# Schematics.net
KiCad netlist of a schematic drawn in Altium Designer
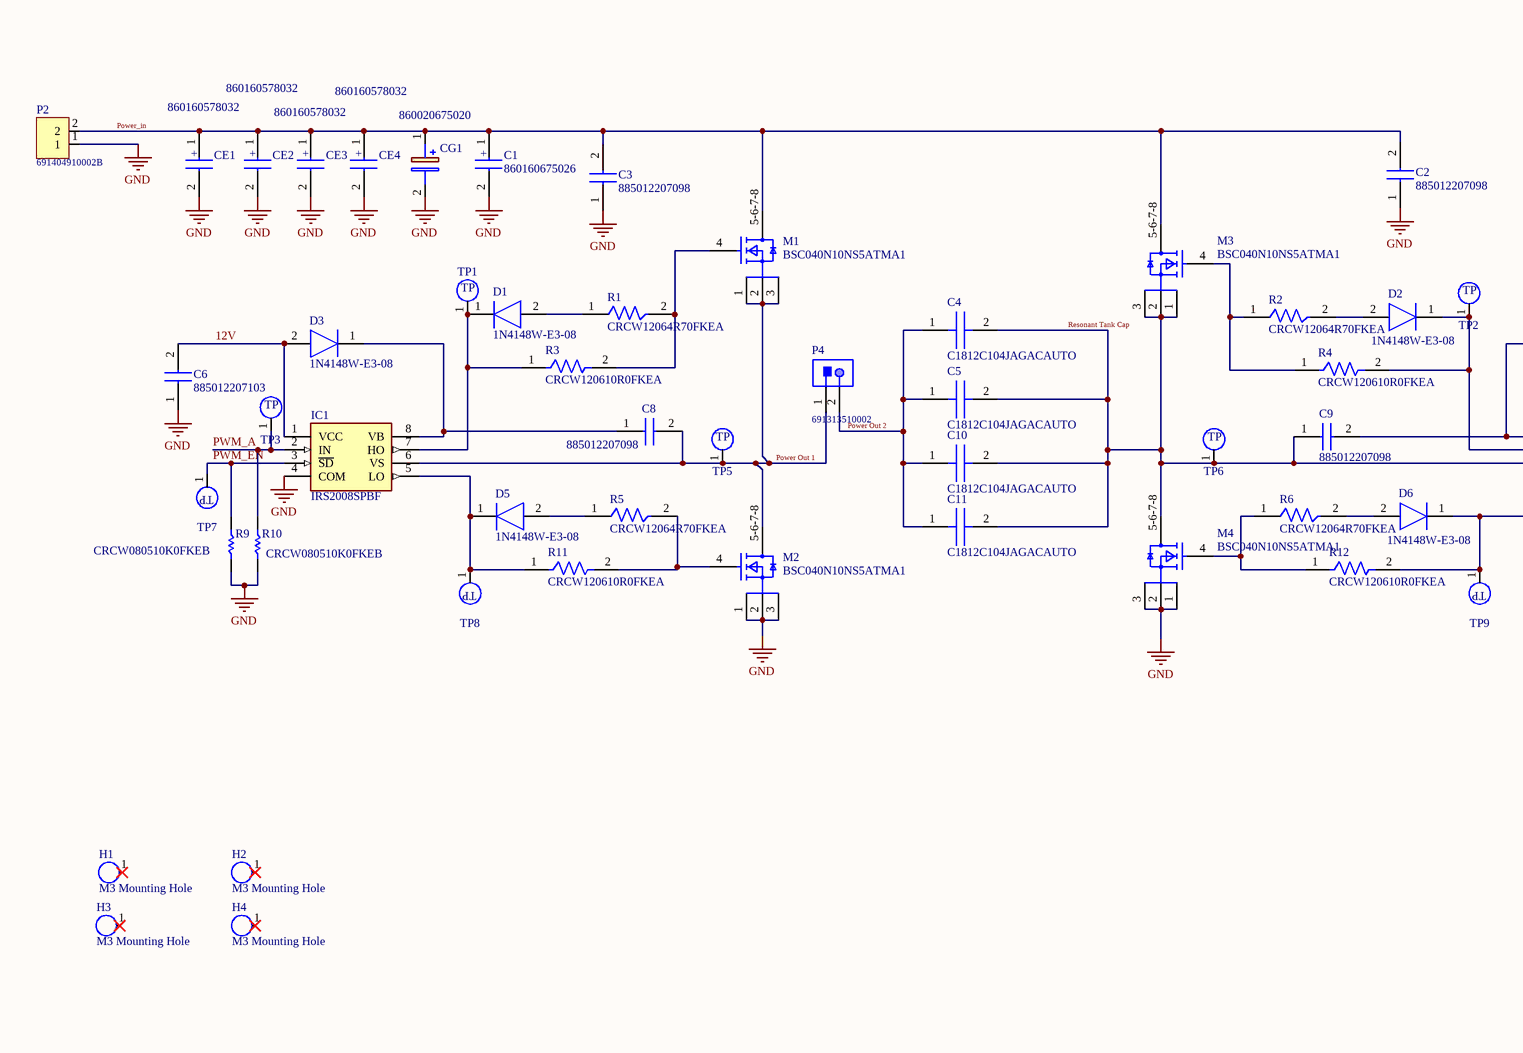
[diagram p0: Schematics.SchDoc, left]
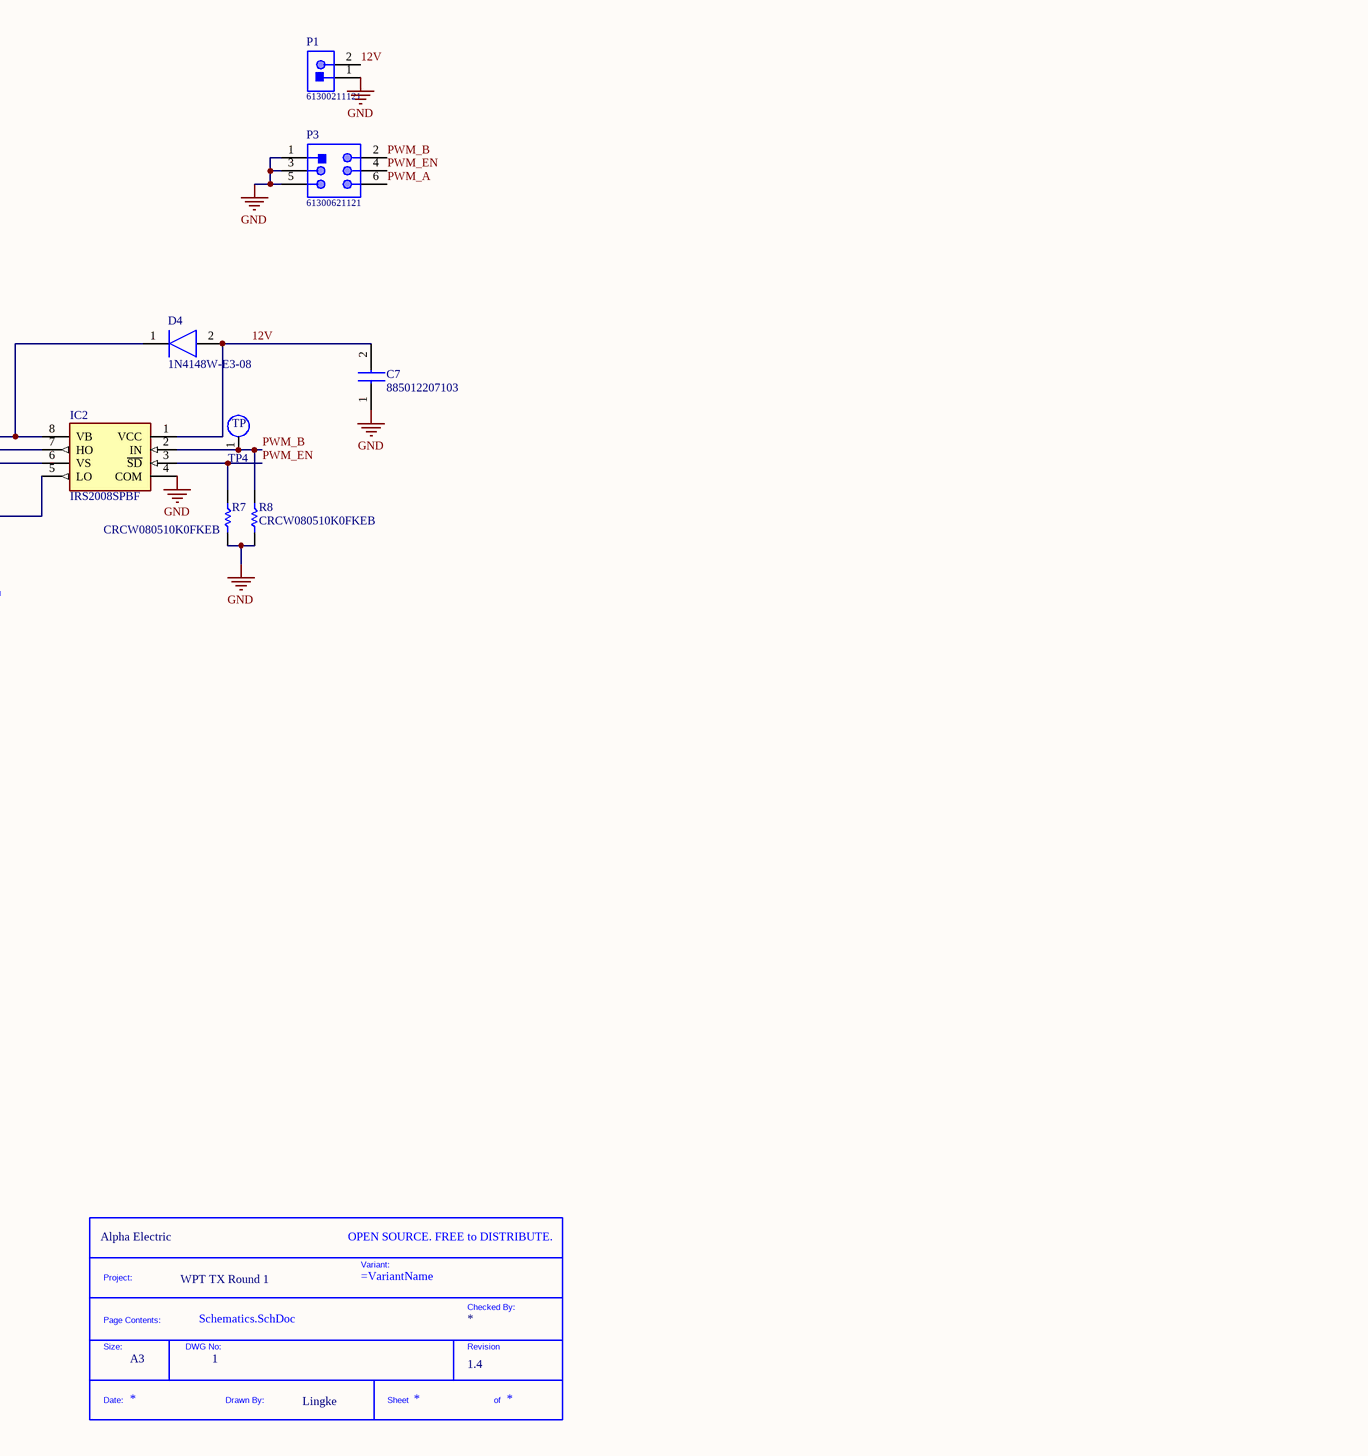
[diagram p1: Schematics.SchDoc, middle]
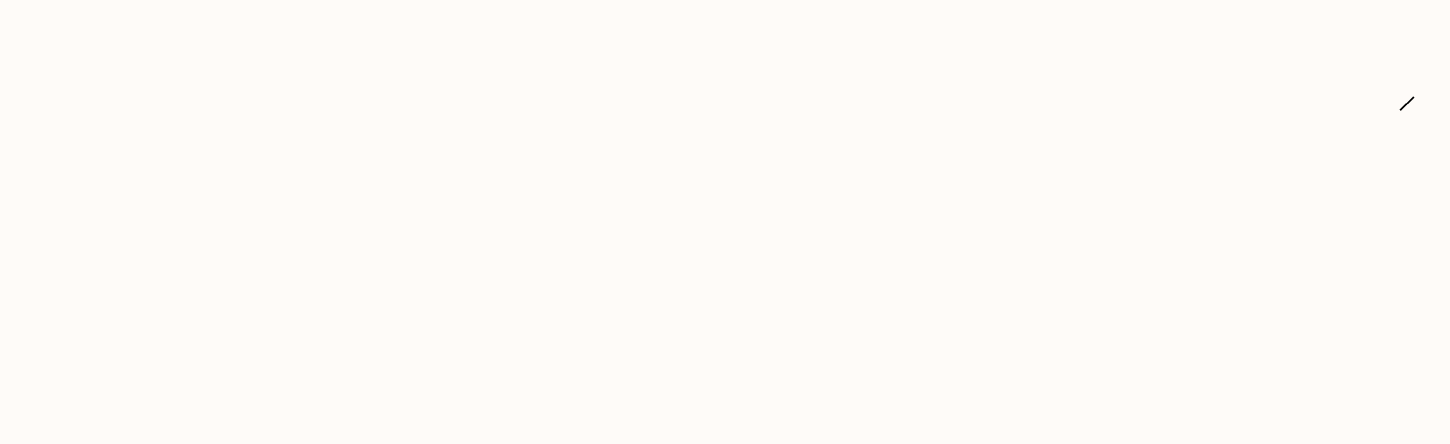
[diagram p2: Schematics.SchDoc, right]

(export (version "E")
  (design (tool "Eeschema 10.0.6"))
  (components
    (comp (ref "*")
      (value "Title_Block")
      (description "Standard Title Block.")
      (fields
        (field (name "PROJECT NAME") "WPT TX Round 1")
        (field (name "COMPANY") "Alpha Electric")
        (field (name "DRAWN BY") "Lingke")
        (field (name "REVISION") "1.4")
        (field (name "DWG NO") "1")
        (field (name "SIZE") "A3")
        (field (name "CHECKED BY") "*")
      )
      (libsource (lib "Symbol Library") (part "Title_Block"))
    )
    (comp (ref "C1")
      (value "860160675026")
      (footprint "SamacSys:CAPPRD500W62D1000H1750")
      (description "Capacitor 220uF/50V")
      (libsource (lib "Symbol Library") (part "Input Cap 220uF"))
    )
    (comp (ref "C2")
      (value "885012207098")
      (footprint "SamacSys:CAPC2012X90N")
      (description "Capacitor 0.1uF/50V X7R")
      (fields (field (name "MOUSER2 PART NUMBER") "710-885012207098"))
      (libsource (lib "Symbol Library") (part "Input Cap 100nF"))
    )
    (comp (ref "C3")
      (value "885012207098")
      (footprint "SamacSys:CAPC2012X90N")
      (description "Capacitor 0.1uF/50V X7R")
      (fields (field (name "MOUSER2 PART NUMBER") "710-885012207098"))
      (libsource (lib "Symbol Library") (part "Input Cap 100nF"))
    )
    (comp (ref "C4")
      (value "C1812C104JAGACAUTO")
      (footprint "SamacSys:CAPC4532X220N")
      (description "Resistor")
      (libsource (lib "Symbol Library") (part "Resonant Tank Cap"))
    )
    (comp (ref "C5")
      (value "C1812C104JAGACAUTO")
      (footprint "SamacSys:CAPC4532X220N")
      (description "Resistor")
      (libsource (lib "Symbol Library") (part "Resonant Tank Cap"))
    )
    (comp (ref "C6")
      (value "885012207103")
      (footprint "SamacSys:CAPC2012X135N")
      (description "Capacitor")
      (libsource (lib "Symbol Library") (part "12V Fiter Cap"))
    )
    (comp (ref "C7")
      (value "885012207103")
      (footprint "SamacSys:CAPC2012X135N")
      (description "Capacitor")
      (libsource (lib "Symbol Library") (part "12V Fiter Cap"))
    )
    (comp (ref "C8")
      (value "885012207098")
      (footprint "SamacSys:CAPC2012X90N")
      (description "Capacitor 0.1uF/50V X7R")
      (fields (field (name "MOUSER2 PART NUMBER") "710-885012207098"))
      (libsource (lib "Symbol Library") (part "Input Cap 100nF"))
    )
    (comp (ref "C9")
      (value "885012207098")
      (footprint "SamacSys:CAPC2012X90N")
      (description "Capacitor 0.1uF/50V X7R")
      (fields (field (name "MOUSER2 PART NUMBER") "710-885012207098"))
      (libsource (lib "") (part "Input Cap 100nF_1"))
    )
    (comp (ref "C10")
      (value "C1812C104JAGACAUTO")
      (footprint "SamacSys:CAPC4532X220N")
      (description "Resistor")
      (libsource (lib "Symbol Library") (part "Resonant Tank Cap"))
    )
    (comp (ref "C11")
      (value "C1812C104JAGACAUTO")
      (footprint "SamacSys:CAPC4532X220N")
      (description "Resistor")
      (libsource (lib "Symbol Library") (part "Resonant Tank Cap"))
    )
    (comp (ref "CE1")
      (value "860160578032")
      (footprint "SamacSys:CAPPRD500W62D1300H2650")
      (description "Capacitor 1000uF Input Filtering")
      (libsource (lib "Symbol Library") (part "1000uF Input Cap"))
    )
    (comp (ref "CE2")
      (value "860160578032")
      (footprint "SamacSys:CAPPRD500W62D1300H2650")
      (description "Capacitor 1000uF Input Filtering")
      (libsource (lib "Symbol Library") (part "1000uF Input Cap"))
    )
    (comp (ref "CE3")
      (value "860160578032")
      (footprint "SamacSys:CAPPRD500W62D1300H2650")
      (description "Capacitor 1000uF Input Filtering")
      (libsource (lib "Symbol Library") (part "1000uF Input Cap"))
    )
    (comp (ref "CE4")
      (value "860160578032")
      (footprint "SamacSys:CAPPRD500W62D1300H2650")
      (description "Capacitor 1000uF Input Filtering")
      (libsource (lib "Symbol Library") (part "1000uF Input Cap"))
    )
    (comp (ref "CG1")
      (value "860020675020")
      (footprint "SamacSys:CAPPRD500W62D1000H1400")
      (description "Capacitor Polarised")
      (libsource (lib "Symbol Library") (part "Ground Splitting Cap"))
    )
    (comp (ref "D1")
      (value "1N4148W-E3-08")
      (footprint "SamacSys:SOD3716X135N")
      (description "Diode")
      (fields (field (name "MOUSER2 PART NUMBER") "78-1N4148W-E3-08"))
      (libsource (lib "Symbol Library") (part "BootStrap Diode"))
    )
    (comp (ref "D2")
      (value "1N4148W-E3-08")
      (footprint "SamacSys:SOD3716X135N")
      (description "Diode")
      (fields (field (name "MOUSER2 PART NUMBER") "78-1N4148W-E3-08"))
      (libsource (lib "Symbol Library") (part "BootStrap Diode"))
    )
    (comp (ref "D3")
      (value "1N4148W-E3-08")
      (footprint "SamacSys:SOD3716X135N")
      (description "Diode")
      (fields (field (name "MOUSER2 PART NUMBER") "78-1N4148W-E3-08"))
      (libsource (lib "Symbol Library") (part "BootStrap Diode"))
    )
    (comp (ref "D4")
      (value "1N4148W-E3-08")
      (footprint "SamacSys:SOD3716X135N")
      (description "Diode")
      (fields (field (name "MOUSER2 PART NUMBER") "78-1N4148W-E3-08"))
      (libsource (lib "Symbol Library") (part "BootStrap Diode"))
    )
    (comp (ref "D5")
      (value "1N4148W-E3-08")
      (footprint "SamacSys:SOD3716X135N")
      (description "Diode")
      (fields (field (name "MOUSER2 PART NUMBER") "78-1N4148W-E3-08"))
      (libsource (lib "Symbol Library") (part "BootStrap Diode"))
    )
    (comp (ref "D6")
      (value "1N4148W-E3-08")
      (footprint "SamacSys:SOD3716X135N")
      (description "Diode")
      (fields (field (name "MOUSER2 PART NUMBER") "78-1N4148W-E3-08"))
      (libsource (lib "Symbol Library") (part "BootStrap Diode"))
    )
    (comp (ref "H1")
      (value "M3 Mounting Hole")
      (footprint "M3 Hole")
      (libsource (lib "Symbol Library") (part "M3_Mounting_hole"))
    )
    (comp (ref "H2")
      (value "M3 Mounting Hole")
      (footprint "M3 Hole")
      (libsource (lib "Symbol Library") (part "M3_Mounting_hole"))
    )
    (comp (ref "H3")
      (value "M3 Mounting Hole")
      (footprint "M3 Hole")
      (libsource (lib "Symbol Library") (part "M3_Mounting_hole"))
    )
    (comp (ref "H4")
      (value "M3 Mounting Hole")
      (footprint "M3 Hole")
      (libsource (lib "Symbol Library") (part "M3_Mounting_hole"))
    )
    (comp (ref "IC1")
      (value "IRS2008SPBF")
      (footprint "SamacSys:SOIC127P600X175-8N")
      (description "Integrated Circuit")
      (libsource (lib "") (part "Gate Driver IC_1"))
    )
    (comp (ref "IC2")
      (value "IRS2008SPBF")
      (footprint "SamacSys:SOIC127P600X175-8N")
      (description "Integrated Circuit")
      (libsource (lib "Symbol Library") (part "Gate Driver IC"))
    )
    (comp (ref "M1")
      (value "BSC040N10NS5ATMA1")
      (footprint "FP-PG-TDSON-8-MFG")
      (description "MOSFET N-CH 100V 100A 8TDSON")
      (fields
        (field (name "MANUFACTURER") "Infineon")
        (field (name "OCTOPART") "https://octopart.com/bsc040n10ns5atma1-infineon-52825711")
      )
      (libsource (lib "Symbol Library") (part "Mosfet Switcher"))
    )
    (comp (ref "M2")
      (value "BSC040N10NS5ATMA1")
      (footprint "FP-PG-TDSON-8-MFG")
      (description "MOSFET N-CH 100V 100A 8TDSON")
      (fields
        (field (name "MANUFACTURER") "Infineon")
        (field (name "OCTOPART") "https://octopart.com/bsc040n10ns5atma1-infineon-52825711")
      )
      (libsource (lib "Symbol Library") (part "Mosfet Switcher"))
    )
    (comp (ref "M3")
      (value "BSC040N10NS5ATMA1")
      (footprint "FP-PG-TDSON-8-MFG")
      (description "MOSFET N-CH 100V 100A 8TDSON")
      (fields
        (field (name "MANUFACTURER") "Infineon")
        (field (name "OCTOPART") "https://octopart.com/bsc040n10ns5atma1-infineon-52825711")
      )
      (libsource (lib "Symbol Library") (part "Mosfet Switcher"))
    )
    (comp (ref "M4")
      (value "BSC040N10NS5ATMA1")
      (footprint "FP-PG-TDSON-8-MFG")
      (description "MOSFET N-CH 100V 100A 8TDSON")
      (fields
        (field (name "MANUFACTURER") "Infineon")
        (field (name "OCTOPART") "https://octopart.com/bsc040n10ns5atma1-infineon-52825711")
      )
      (libsource (lib "Symbol Library") (part "Mosfet Switcher"))
    )
    (comp (ref "P1")
      (value "61300211121")
      (footprint "61300211121")
      (description "THT Vertical Pin Header WR-PHD, Pitch 2.54 mm, Single Row, 2 pins")
      (fields (field (name "MANUFACTURER") "Wurth Elektronik") (field (name "PUBLISHER") "WurthElektronik"))
      (libsource (lib "Symbol Library") (part "12V Input"))
    )
    (comp (ref "P2")
      (value "691404910002B")
      (footprint "691404910002B")
      (description "Serie 4049 B - 7.50mm Screwless Clamp Power Connector WR-TBL, 2 pin")
      (fields (field (name "MANUFACTURER") "Wurth Elektronik") (field (name "PUBLISHER") "WurthElektronik"))
      (libsource (lib "Symbol Library") (part "Power Input"))
    )
    (comp (ref "P3")
      (value "61300621121")
      (footprint "61300621121")
      (description "THT Vertical Pin Header WR-PHD, Pitch 2.54 mm, Dual Row, 6 pins")
      (fields (field (name "MANUFACTURER") "Wurth Elektronik") (field (name "PUBLISHER") "WurthElektronik"))
      (libsource (lib "Symbol Library") (part "PWM Input Dual Pin"))
    )
    (comp (ref "P4")
      (value "691313510002")
      (footprint "691313510002")
      (description "Serie 313 - 5.08mm Close Horizontal PCB Header WR-TBL, 2 pin")
      (fields (field (name "MANUFACTURER") "Wurth Elektronik") (field (name "PUBLISHER") "WurthElektronik"))
      (libsource (lib "Symbol Library") (part "Power Output"))
    )
    (comp (ref "R1")
      (value "CRCW12064R70FKEA")
      (footprint "FP-CRCW1206-e3-IPC_A")
      (description "RES Thick Film, 4.7Ω, 1%, 0.25W, 100ppm/°C, 1206")
      (fields (field (name "TOLERANCE") "1%"))
      (libsource (lib "") (part "MOSFET Gate Fast-off Resistor 4.7Ohm_1"))
    )
    (comp (ref "R2")
      (value "CRCW12064R70FKEA")
      (footprint "FP-CRCW1206-e3-IPC_A")
      (description "RES Thick Film, 4.7Ω, 1%, 0.25W, 100ppm/°C, 1206")
      (fields (field (name "TOLERANCE") "1%"))
      (libsource (lib "Symbol Library") (part "MOSFET Gate Fast-off Resistor 4.7Ohm"))
    )
    (comp (ref "R3")
      (value "CRCW120610R0FKEA")
      (footprint "FP-CRCW1206-e3-IPC_A")
      (description "RES Thick Film, 10Ω, 1%, 0.25W, 100ppm/°C, 1206")
      (fields (field (name "TOLERANCE") "1%"))
      (libsource (lib "Symbol Library") (part "MOSFET Gate Resistor 10Ohm"))
    )
    (comp (ref "R4")
      (value "CRCW120610R0FKEA")
      (footprint "FP-CRCW1206-e3-IPC_A")
      (description "RES Thick Film, 10Ω, 1%, 0.25W, 100ppm/°C, 1206")
      (fields (field (name "TOLERANCE") "1%"))
      (libsource (lib "") (part "MOSFET Gate Resistor 10Ohm_1"))
    )
    (comp (ref "R5")
      (value "CRCW12064R70FKEA")
      (footprint "FP-CRCW1206-e3-IPC_A")
      (description "RES Thick Film, 4.7Ω, 1%, 0.25W, 100ppm/°C, 1206")
      (fields (field (name "TOLERANCE") "1%"))
      (libsource (lib "") (part "MOSFET Gate Fast-off Resistor 4.7Ohm_1"))
    )
    (comp (ref "R6")
      (value "CRCW12064R70FKEA")
      (footprint "FP-CRCW1206-e3-IPC_A")
      (description "RES Thick Film, 4.7Ω, 1%, 0.25W, 100ppm/°C, 1206")
      (fields (field (name "TOLERANCE") "1%"))
      (libsource (lib "Symbol Library") (part "MOSFET Gate Fast-off Resistor 4.7Ohm"))
    )
    (comp (ref "R7")
      (value "CRCW080510K0FKEB")
      (footprint "RESC2013X50X30ML20T20")
      (fields (field (name "MANUFACTURER") "Vishay Dale"))
      (libsource (lib "Symbol Library") (part "PWM Pull Down Resistor"))
    )
    (comp (ref "R8")
      (value "CRCW080510K0FKEB")
      (footprint "RESC2013X50X30ML20T20")
      (fields (field (name "MANUFACTURER") "Vishay Dale"))
      (libsource (lib "Symbol Library") (part "PWM Pull Down Resistor"))
    )
    (comp (ref "R9")
      (value "CRCW080510K0FKEB")
      (footprint "RESC2013X50X30ML20T20")
      (fields (field (name "MANUFACTURER") "Vishay Dale"))
      (libsource (lib "Symbol Library") (part "PWM Pull Down Resistor"))
    )
    (comp (ref "R10")
      (value "CRCW080510K0FKEB")
      (footprint "RESC2013X50X30ML20T20")
      (fields (field (name "MANUFACTURER") "Vishay Dale"))
      (libsource (lib "Symbol Library") (part "PWM Pull Down Resistor"))
    )
    (comp (ref "R11")
      (value "CRCW120610R0FKEA")
      (footprint "FP-CRCW1206-e3-IPC_A")
      (description "RES Thick Film, 10Ω, 1%, 0.25W, 100ppm/°C, 1206")
      (fields (field (name "TOLERANCE") "1%"))
      (libsource (lib "Symbol Library") (part "MOSFET Gate Resistor 10Ohm"))
    )
    (comp (ref "R12")
      (value "CRCW120610R0FKEA")
      (footprint "FP-CRCW1206-e3-IPC_A")
      (description "RES Thick Film, 10Ω, 1%, 0.25W, 100ppm/°C, 1206")
      (fields (field (name "TOLERANCE") "1%"))
      (libsource (lib "") (part "MOSFET Gate Resistor 10Ohm_1"))
    )
    (comp (ref "TP1")
      (value "TP")
      (footprint "Test Point")
      (description "Test Point 1mm by 1mm")
      (libsource (lib "Symbol Library") (part "Test Point"))
    )
    (comp (ref "TP2")
      (value "TP")
      (footprint "Test Point")
      (description "Test Point 1mm by 1mm")
      (libsource (lib "Symbol Library") (part "Test Point"))
    )
    (comp (ref "TP3")
      (value "TP")
      (footprint "Test Point")
      (description "Test Point 1mm by 1mm")
      (libsource (lib "Symbol Library") (part "Test Point"))
    )
    (comp (ref "TP4")
      (value "TP")
      (footprint "Test Point")
      (description "Test Point 1mm by 1mm")
      (libsource (lib "Symbol Library") (part "Test Point"))
    )
    (comp (ref "TP5")
      (value "TP")
      (footprint "Test Point")
      (description "Test Point 1mm by 1mm")
      (libsource (lib "Symbol Library") (part "Test Point"))
    )
    (comp (ref "TP6")
      (value "TP")
      (footprint "Test Point")
      (description "Test Point 1mm by 1mm")
      (libsource (lib "Symbol Library") (part "Test Point"))
    )
    (comp (ref "TP7")
      (value "TP")
      (footprint "Test Point")
      (description "Test Point 1mm by 1mm")
      (libsource (lib "Symbol Library") (part "Test Point"))
    )
    (comp (ref "TP8")
      (value "TP")
      (footprint "Test Point")
      (description "Test Point 1mm by 1mm")
      (libsource (lib "Symbol Library") (part "Test Point"))
    )
    (comp (ref "TP9")
      (value "TP")
      (footprint "Test Point")
      (description "Test Point 1mm by 1mm")
      (libsource (lib "Symbol Library") (part "Test Point"))
    )
  )
  (nets
    (net (code "1") (name "/12V") (class "Default")
      (node (ref "C6") (pin "2") (pinfunction "2_2") (pintype "passive"))
      (node (ref "C7") (pin "2") (pinfunction "2_2") (pintype "passive"))
      (node (ref "D3") (pin "2") (pinfunction "A_2") (pintype "passive"))
      (node (ref "D4") (pin "2") (pinfunction "A_2") (pintype "passive"))
      (node (ref "IC1") (pin "1") (pinfunction "VCC_1") (pintype "power_in"))
      (node (ref "IC2") (pin "1") (pinfunction "VCC_1") (pintype "power_in"))
      (node (ref "P1") (pin "2") (pinfunction "2_2") (pintype "passive"))
    )
    (net (code "2") (name "/PWM_A") (class "Default")
      (node (ref "IC1") (pin "2") (pinfunction "IN_2") (pintype "input"))
      (node (ref "P3") (pin "6") (pinfunction "6_6") (pintype "passive"))
      (node (ref "R10") (pin "2") (pinfunction "2_2") (pintype "passive"))
      (node (ref "TP3") (pin "1") (pinfunction "TP_1") (pintype "passive"))
    )
    (net (code "3") (name "/PWM_B") (class "Default")
      (node (ref "IC2") (pin "2") (pinfunction "IN_2") (pintype "input"))
      (node (ref "P3") (pin "2") (pinfunction "2_2") (pintype "passive"))
      (node (ref "R8") (pin "2") (pinfunction "2_2") (pintype "passive"))
      (node (ref "TP4") (pin "1") (pinfunction "TP_1") (pintype "passive"))
    )
    (net (code "4") (name "/PWM_EN") (class "Default")
      (node (ref "IC1") (pin "3") (pinfunction "~{SD}_3") (pintype "input"))
      (node (ref "IC2") (pin "3") (pinfunction "~{SD}_3") (pintype "input"))
      (node (ref "P3") (pin "4") (pinfunction "4_4") (pintype "passive"))
      (node (ref "R7") (pin "2") (pinfunction "2_2") (pintype "passive"))
      (node (ref "R9") (pin "2") (pinfunction "2_2") (pintype "passive"))
      (node (ref "TP7") (pin "1") (pinfunction "TP_1") (pintype "passive"))
    )
    (net (code "5") (name "/Power Out 1") (class "Default")
      (node (ref "C8") (pin "2") (pinfunction "2_2") (pintype "passive"))
      (node (ref "IC1") (pin "6") (pinfunction "VS_6") (pintype "power_in"))
      (node (ref "M1") (pin "1") (pinfunction "S_1") (pintype "passive"))
      (node (ref "M1") (pin "2") (pinfunction "S_2") (pintype "passive"))
      (node (ref "M1") (pin "3") (pinfunction "S_3") (pintype "passive"))
      (node (ref "M2") (pin "5-6-7-8") (pinfunction "D_5-6-7-8") (pintype "passive"))
      (node (ref "P4") (pin "1") (pinfunction "1_1") (pintype "passive"))
      (node (ref "TP5") (pin "1") (pinfunction "TP_1") (pintype "passive"))
    )
    (net (code "6") (name "/Power Out 2") (class "Default")
      (node (ref "C10") (pin "1") (pinfunction "1_1") (pintype "passive"))
      (node (ref "C11") (pin "1") (pinfunction "1_1") (pintype "passive"))
      (node (ref "C4") (pin "1") (pinfunction "1_1") (pintype "passive"))
      (node (ref "C5") (pin "1") (pinfunction "1_1") (pintype "passive"))
      (node (ref "P4") (pin "2") (pinfunction "2_2") (pintype "passive"))
    )
    (net (code "7") (name "/Power_in") (class "Default")
      (node (ref "C1") (pin "1") (pinfunction "+_1") (pintype "passive"))
      (node (ref "C2") (pin "2") (pinfunction "2_2") (pintype "passive"))
      (node (ref "C3") (pin "2") (pinfunction "2_2") (pintype "passive"))
      (node (ref "CE1") (pin "1") (pinfunction "+_1") (pintype "passive"))
      (node (ref "CE2") (pin "1") (pinfunction "+_1") (pintype "passive"))
      (node (ref "CE3") (pin "1") (pinfunction "+_1") (pintype "passive"))
      (node (ref "CE4") (pin "1") (pinfunction "+_1") (pintype "passive"))
      (node (ref "CG1") (pin "1") (pinfunction "+_1") (pintype "passive"))
      (node (ref "M1") (pin "5-6-7-8") (pinfunction "D_5-6-7-8") (pintype "passive"))
      (node (ref "M3") (pin "5-6-7-8") (pinfunction "D_5-6-7-8") (pintype "passive"))
      (node (ref "P2") (pin "2") (pinfunction "2_2") (pintype "passive"))
    )
    (net (code "8") (name "/Resonant Tank Cap") (class "Default")
      (node (ref "C10") (pin "2") (pinfunction "2_2") (pintype "passive"))
      (node (ref "C11") (pin "2") (pinfunction "2_2") (pintype "passive"))
      (node (ref "C4") (pin "2") (pinfunction "2_2") (pintype "passive"))
      (node (ref "C5") (pin "2") (pinfunction "2_2") (pintype "passive"))
      (node (ref "C9") (pin "1") (pinfunction "1_1") (pintype "passive"))
      (node (ref "IC2") (pin "6") (pinfunction "VS_6") (pintype "power_in"))
      (node (ref "M3") (pin "1") (pinfunction "S_1") (pintype "passive"))
      (node (ref "M3") (pin "2") (pinfunction "S_2") (pintype "passive"))
      (node (ref "M3") (pin "3") (pinfunction "S_3") (pintype "passive"))
      (node (ref "M4") (pin "5-6-7-8") (pinfunction "D_5-6-7-8") (pintype "passive"))
      (node (ref "TP6") (pin "1") (pinfunction "TP_1") (pintype "passive"))
    )
    (net (code "9") (name "GND") (class "Default")
      (node (ref "C1") (pin "2") (pinfunction "-_2") (pintype "passive"))
      (node (ref "C2") (pin "1") (pinfunction "1_1") (pintype "passive"))
      (node (ref "C3") (pin "1") (pinfunction "1_1") (pintype "passive"))
      (node (ref "C6") (pin "1") (pinfunction "1_1") (pintype "passive"))
      (node (ref "C7") (pin "1") (pinfunction "1_1") (pintype "passive"))
      (node (ref "CE1") (pin "2") (pinfunction "-_2") (pintype "passive"))
      (node (ref "CE2") (pin "2") (pinfunction "-_2") (pintype "passive"))
      (node (ref "CE3") (pin "2") (pinfunction "-_2") (pintype "passive"))
      (node (ref "CE4") (pin "2") (pinfunction "-_2") (pintype "passive"))
      (node (ref "CG1") (pin "2") (pinfunction "-_2") (pintype "passive"))
      (node (ref "IC1") (pin "4") (pinfunction "COM_4") (pintype "power_in"))
      (node (ref "IC2") (pin "4") (pinfunction "COM_4") (pintype "power_in"))
      (node (ref "M2") (pin "1") (pinfunction "S_1") (pintype "passive"))
      (node (ref "M2") (pin "2") (pinfunction "S_2") (pintype "passive"))
      (node (ref "M2") (pin "3") (pinfunction "S_3") (pintype "passive"))
      (node (ref "M4") (pin "1") (pinfunction "S_1") (pintype "passive"))
      (node (ref "M4") (pin "2") (pinfunction "S_2") (pintype "passive"))
      (node (ref "M4") (pin "3") (pinfunction "S_3") (pintype "passive"))
      (node (ref "P1") (pin "1") (pinfunction "1_1") (pintype "passive"))
      (node (ref "P2") (pin "1") (pinfunction "1_1") (pintype "passive"))
      (node (ref "P3") (pin "1") (pinfunction "1_1") (pintype "passive"))
      (node (ref "P3") (pin "3") (pinfunction "3_3") (pintype "passive"))
      (node (ref "P3") (pin "5") (pinfunction "5_5") (pintype "passive"))
      (node (ref "R10") (pin "1") (pinfunction "1_1") (pintype "passive"))
      (node (ref "R7") (pin "1") (pinfunction "1_1") (pintype "passive"))
      (node (ref "R8") (pin "1") (pinfunction "1_1") (pintype "passive"))
      (node (ref "R9") (pin "1") (pinfunction "1_1") (pintype "passive"))
    )
    (net (code "10") (name "Net-(D1-A)") (class "Default")
      (node (ref "D1") (pin "2") (pinfunction "A_2") (pintype "passive"))
      (node (ref "R1") (pin "1") (pinfunction "1_1") (pintype "passive"))
    )
    (net (code "11") (name "Net-(D1-K)") (class "Default")
      (node (ref "D1") (pin "1") (pinfunction "K_1") (pintype "passive"))
      (node (ref "IC1") (pin "7") (pinfunction "HO_7") (pintype "output"))
      (node (ref "R3") (pin "1") (pinfunction "1_1") (pintype "passive"))
      (node (ref "TP1") (pin "1") (pinfunction "TP_1") (pintype "passive"))
    )
    (net (code "12") (name "Net-(D2-A)") (class "Default")
      (node (ref "D2") (pin "2") (pinfunction "A_2") (pintype "passive"))
      (node (ref "R2") (pin "2") (pinfunction "2_2") (pintype "passive"))
    )
    (net (code "13") (name "Net-(D2-K)") (class "Default")
      (node (ref "D2") (pin "1") (pinfunction "K_1") (pintype "passive"))
      (node (ref "IC2") (pin "7") (pinfunction "HO_7") (pintype "output"))
      (node (ref "R4") (pin "2") (pinfunction "2_2") (pintype "passive"))
      (node (ref "TP2") (pin "1") (pinfunction "TP_1") (pintype "passive"))
    )
    (net (code "14") (name "Net-(D3-K)") (class "Default")
      (node (ref "C8") (pin "1") (pinfunction "1_1") (pintype "passive"))
      (node (ref "D3") (pin "1") (pinfunction "K_1") (pintype "passive"))
      (node (ref "IC1") (pin "8") (pinfunction "VB_8") (pintype "power_in"))
    )
    (net (code "15") (name "Net-(D4-K)") (class "Default")
      (node (ref "C9") (pin "2") (pinfunction "2_2") (pintype "passive"))
      (node (ref "D4") (pin "1") (pinfunction "K_1") (pintype "passive"))
      (node (ref "IC2") (pin "8") (pinfunction "VB_8") (pintype "power_in"))
    )
    (net (code "16") (name "Net-(D5-A)") (class "Default")
      (node (ref "D5") (pin "2") (pinfunction "A_2") (pintype "passive"))
      (node (ref "R5") (pin "1") (pinfunction "1_1") (pintype "passive"))
    )
    (net (code "17") (name "Net-(D5-K)") (class "Default")
      (node (ref "D5") (pin "1") (pinfunction "K_1") (pintype "passive"))
      (node (ref "IC1") (pin "5") (pinfunction "LO_5") (pintype "output"))
      (node (ref "R11") (pin "1") (pinfunction "1_1") (pintype "passive"))
      (node (ref "TP8") (pin "1") (pinfunction "TP_1") (pintype "passive"))
    )
    (net (code "18") (name "Net-(D6-A)") (class "Default")
      (node (ref "D6") (pin "2") (pinfunction "A_2") (pintype "passive"))
      (node (ref "R6") (pin "2") (pinfunction "2_2") (pintype "passive"))
    )
    (net (code "19") (name "Net-(D6-K)") (class "Default")
      (node (ref "D6") (pin "1") (pinfunction "K_1") (pintype "passive"))
      (node (ref "IC2") (pin "5") (pinfunction "LO_5") (pintype "output"))
      (node (ref "R12") (pin "2") (pinfunction "2_2") (pintype "passive"))
      (node (ref "TP9") (pin "1") (pinfunction "TP_1") (pintype "passive"))
    )
    (net (code "20") (name "Net-(M1-G)") (class "Default")
      (node (ref "M1") (pin "4") (pinfunction "G_4") (pintype "passive"))
      (node (ref "R1") (pin "2") (pinfunction "2_2") (pintype "passive"))
      (node (ref "R3") (pin "2") (pinfunction "2_2") (pintype "passive"))
    )
    (net (code "21") (name "Net-(M2-G)") (class "Default")
      (node (ref "M2") (pin "4") (pinfunction "G_4") (pintype "passive"))
      (node (ref "R11") (pin "2") (pinfunction "2_2") (pintype "passive"))
      (node (ref "R5") (pin "2") (pinfunction "2_2") (pintype "passive"))
    )
    (net (code "22") (name "Net-(M3-G)") (class "Default")
      (node (ref "M3") (pin "4") (pinfunction "G_4") (pintype "passive"))
      (node (ref "R2") (pin "1") (pinfunction "1_1") (pintype "passive"))
      (node (ref "R4") (pin "1") (pinfunction "1_1") (pintype "passive"))
    )
    (net (code "23") (name "Net-(M4-G)") (class "Default")
      (node (ref "M4") (pin "4") (pinfunction "G_4") (pintype "passive"))
      (node (ref "R12") (pin "1") (pinfunction "1_1") (pintype "passive"))
      (node (ref "R6") (pin "1") (pinfunction "1_1") (pintype "passive"))
    )
    (net (code "24") (name "unconnected-(H1-Pad1)") (class "Default")
      (node (ref "H1") (pin "1") (pinfunction "1_1") (pintype "passive+no_connect"))
    )
    (net (code "25") (name "unconnected-(H2-Pad1)") (class "Default")
      (node (ref "H2") (pin "1") (pinfunction "1_1") (pintype "passive+no_connect"))
    )
    (net (code "26") (name "unconnected-(H3-Pad1)") (class "Default")
      (node (ref "H3") (pin "1") (pinfunction "1_1") (pintype "passive+no_connect"))
    )
    (net (code "27") (name "unconnected-(H4-Pad1)") (class "Default")
      (node (ref "H4") (pin "1") (pinfunction "1_1") (pintype "passive+no_connect"))
    )
  )
)
